# Analog_Buck.net
KiCad netlist of a schematic drawn in EasyEDA Pro
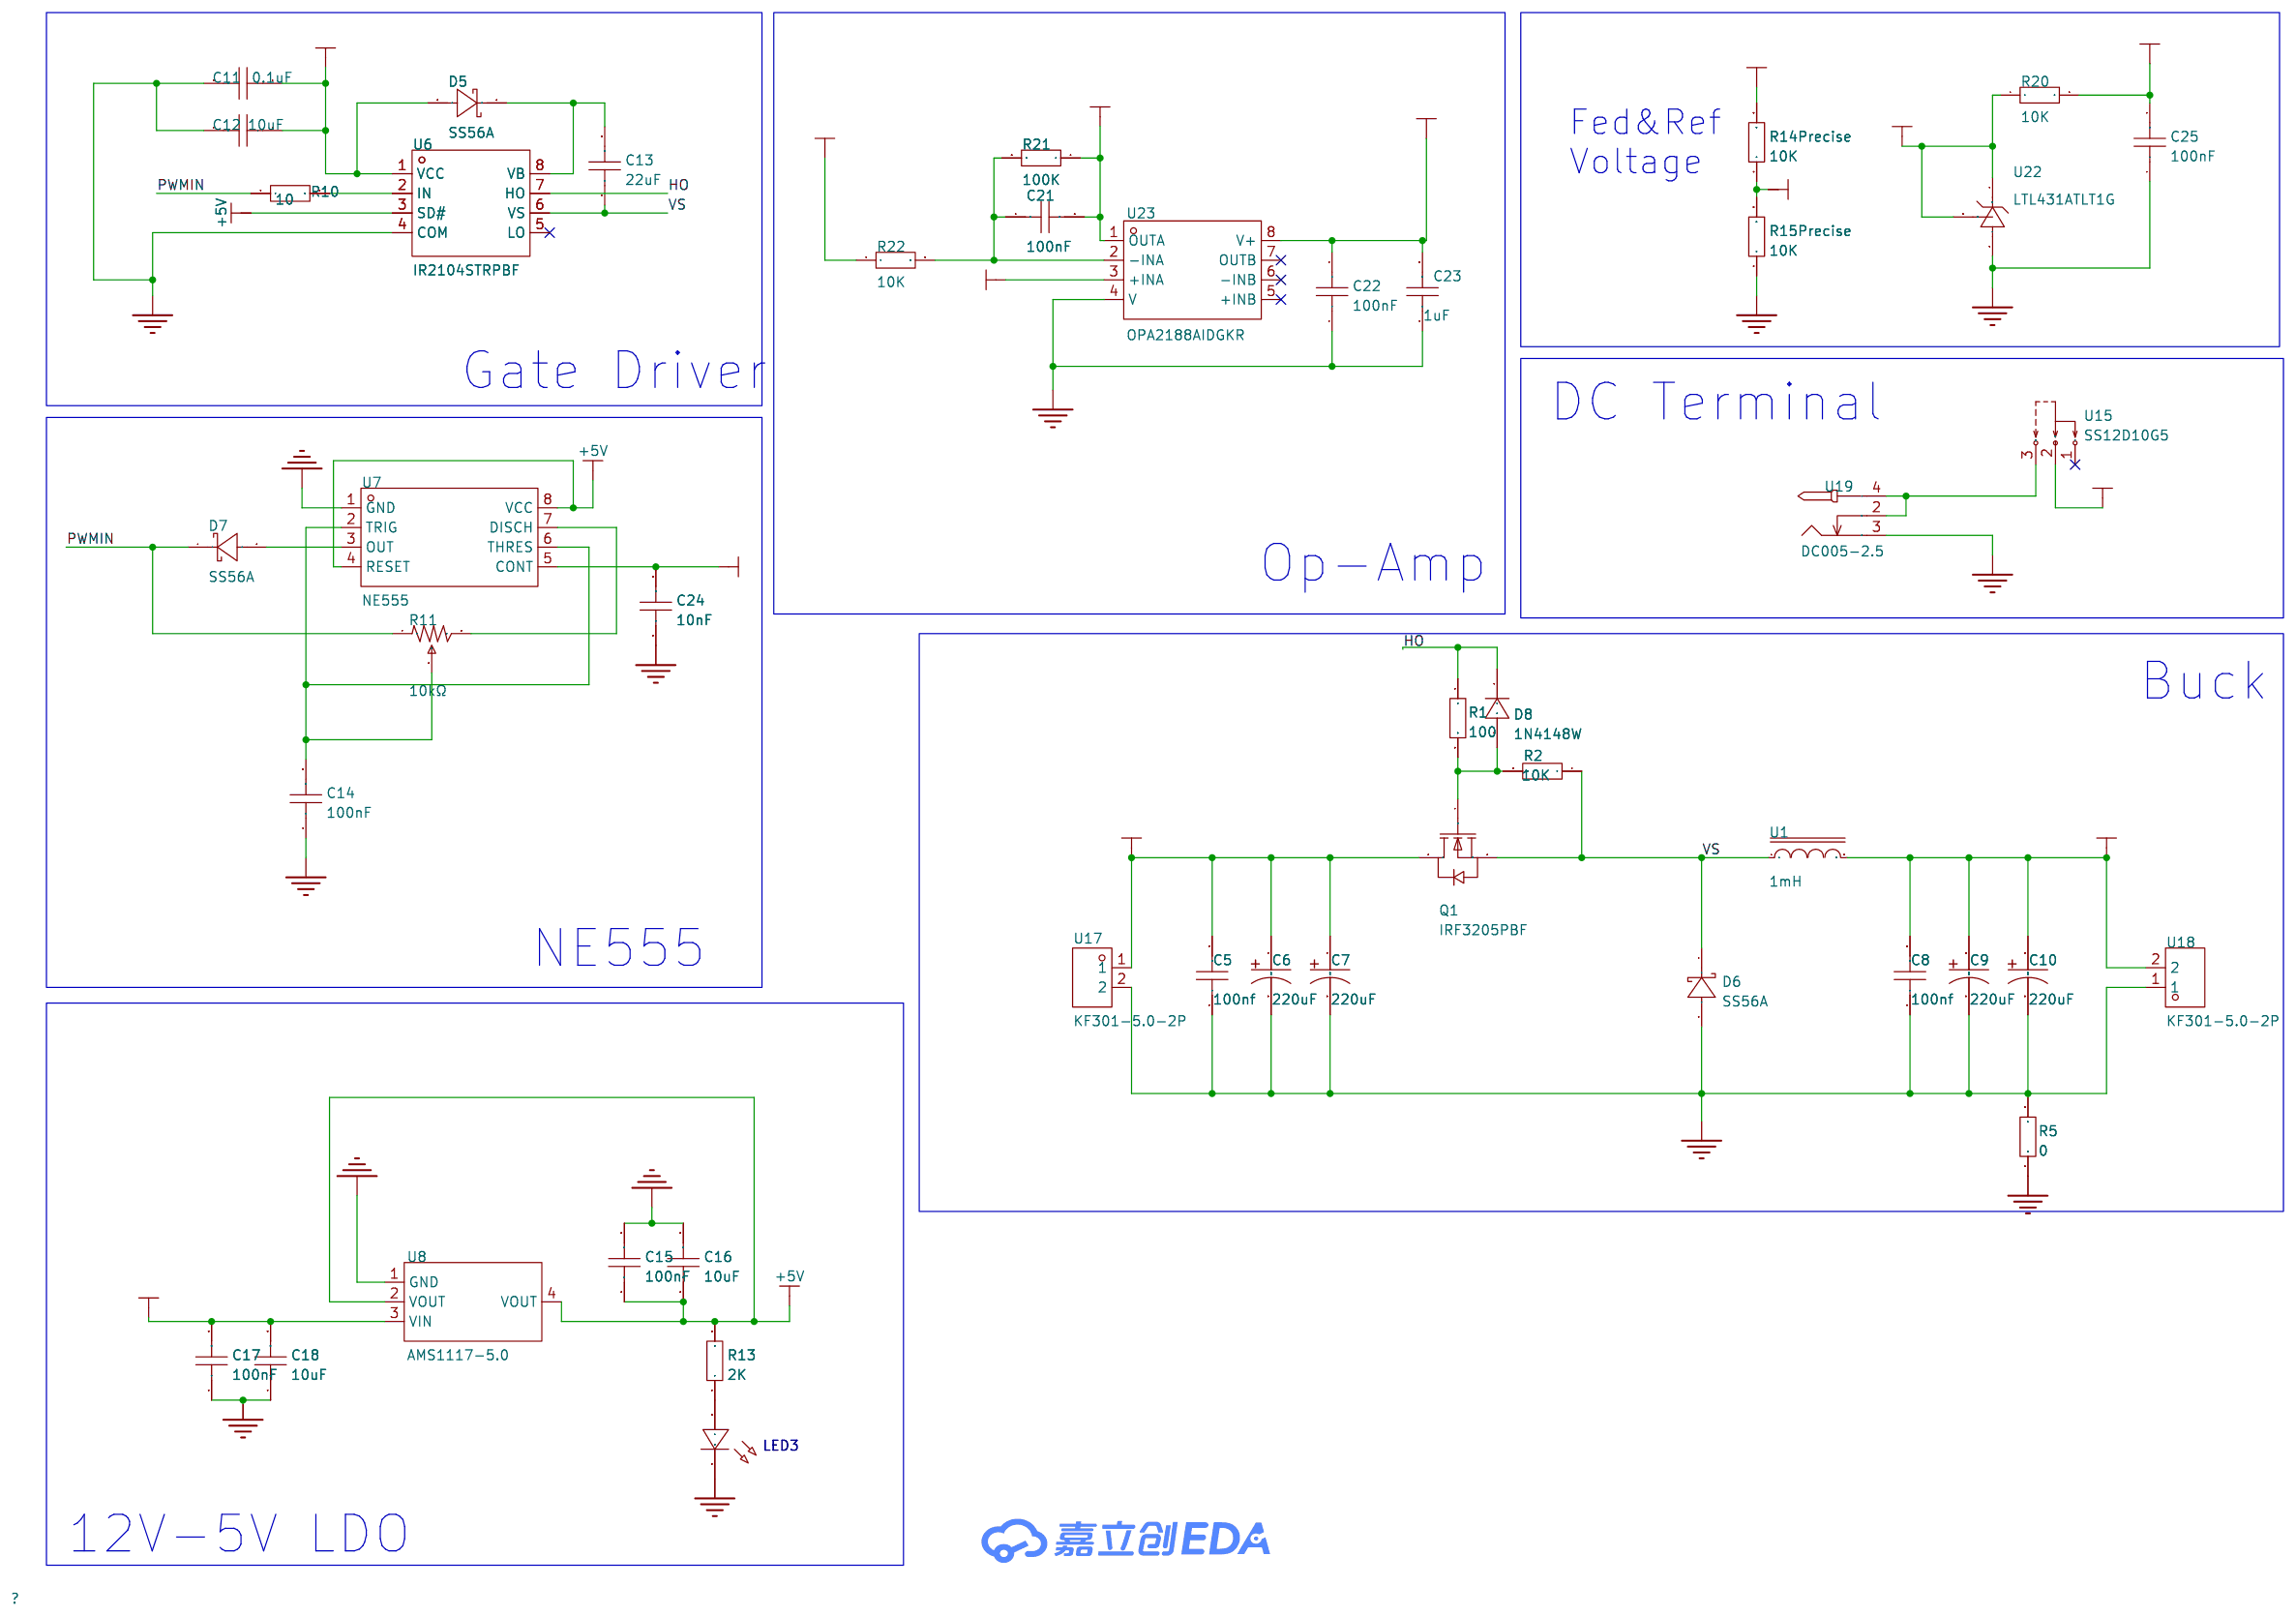
[diagram p0: schematic sheet]

(export (version "E")
  (design (tool "Eeschema 10.0.6"))
  (components
    (comp (ref "C5")
      (value "100nf")
      (footprint "easyedapro:CAP-TH_L8.5-W5.0-P5.00-D1.2")
      (description "容值:100nF;精度:±10%;额定电压:50V;温度系数:X7R;")
      (fields (field (name "Manufacturer Part") "CT4-0805B104K500F3") (field (name "Manufacturer") "FH(风华)"))
      (libsource (lib "easyedapro") (part "CT4-0805B104K500F3"))
    )
    (comp (ref "C6")
      (value "220uF")
      (footprint "easyedapro:CAP-TH_BD10.0-P5.00-D1.0-FD")
      (description "容值:220uF;精度:±20%;额定电压:100V;纹波电流:-;等效串联电阻:-;")
      (fields
        (field (name "Manufacturer Part") "ECF1JM221G17OTPO")
        (field (name "Manufacturer") "Yunxing(云星)")
      )
      (libsource (lib "easyedapro") (part "LKME2502A221MF"))
    )
    (comp (ref "C7")
      (value "220uF")
      (footprint "easyedapro:CAP-TH_BD10.0-P5.00-D1.0-FD")
      (description "容值:220uF;精度:±20%;额定电压:100V;纹波电流:-;等效串联电阻:-;")
      (fields
        (field (name "Manufacturer Part") "ECF1JM221G17OTPO")
        (field (name "Manufacturer") "Yunxing(云星)")
      )
      (libsource (lib "easyedapro") (part "LKME2502A221MF"))
    )
    (comp (ref "C8")
      (value "100nf")
      (footprint "easyedapro:CAP-TH_L8.5-W5.0-P5.00-D1.2")
      (description "容值:100nF;精度:±10%;额定电压:50V;温度系数:X7R;")
      (fields (field (name "Manufacturer Part") "CT4-0805B104K500F3") (field (name "Manufacturer") "FH(风华)"))
      (libsource (lib "easyedapro") (part "CT4-0805B104K500F3"))
    )
    (comp (ref "C9")
      (value "220uF")
      (footprint "easyedapro:CAP-TH_BD10.0-P5.00-D1.0-FD")
      (description "容值:220uF;精度:±20%;额定电压:100V;纹波电流:-;等效串联电阻:-;")
      (fields
        (field (name "Manufacturer Part") "ECF1JM221G17OTPO")
        (field (name "Manufacturer") "Yunxing(云星)")
      )
      (libsource (lib "easyedapro") (part "LKME2502A221MF"))
    )
    (comp (ref "C10")
      (value "220uF")
      (footprint "easyedapro:CAP-TH_BD10.0-P5.00-D1.0-FD")
      (description "容值:220uF;精度:±20%;额定电压:100V;纹波电流:-;等效串联电阻:-;")
      (fields
        (field (name "Manufacturer Part") "ECF1JM221G17OTPO")
        (field (name "Manufacturer") "Yunxing(云星)")
      )
      (libsource (lib "easyedapro") (part "LKME2502A221MF"))
    )
    (comp (ref "C11")
      (value "0.1uF")
      (footprint "easyedapro:C0603")
      (libsource (lib "easyedapro") (part "Capacitance"))
    )
    (comp (ref "C12")
      (value "10uF")
      (footprint "easyedapro:C0603")
      (libsource (lib "easyedapro") (part "Capacitance"))
    )
    (comp (ref "C13")
      (value "22uF")
      (fields
        (field (name "Manufacturer Part") "CD1H225KC9BER1F100")
        (field (name "Manufacturer") "Dersonic(德尔创)")
      )
      (libsource (lib "easyedapro") (part "CT40805B104K500F3"))
    )
    (comp (ref "C14")
      (value "100nF")
      (footprint "easyedapro:C0603")
      (libsource (lib "easyedapro") (part "Capacitance"))
    )
    (comp (ref "C15")
      (value "100nF")
      (footprint "easyedapro:C0603")
      (libsource (lib "easyedapro") (part "Capacitance"))
    )
    (comp (ref "C16")
      (value "10uF")
      (footprint "easyedapro:C0603")
      (libsource (lib "easyedapro") (part "Capacitance"))
    )
    (comp (ref "C17")
      (value "100nF")
      (footprint "easyedapro:C0603")
      (libsource (lib "easyedapro") (part "Capacitance"))
    )
    (comp (ref "C18")
      (value "10uF")
      (footprint "easyedapro:C0603")
      (libsource (lib "easyedapro") (part "Capacitance"))
    )
    (comp (ref "C21")
      (value "100nF")
      (footprint "easyedapro:C0603")
      (libsource (lib "easyedapro") (part "Capacitance"))
    )
    (comp (ref "C22") (value "100nF") (libsource (lib "easyedapro") (part "CapAcitance")))
    (comp (ref "C23") (value "1uF") (libsource (lib "easyedapro") (part "CapAcitance")))
    (comp (ref "C24")
      (value "10nF")
      (footprint "easyedapro:C0603")
      (libsource (lib "easyedapro") (part "Capacitance"))
    )
    (comp (ref "C25") (value "100nF") (libsource (lib "easyedapro") (part "CapAcitance")))
    (comp (ref "D5")
      (value "SS56A")
      (footprint "easyedapro:SMA_L4.2-W2.6-LS5.0-RD")
      (description "二极管配置:独立式;正向压降(Vf):700mV@5A;直流反向耐压(Vr):60V;整流电流:5A;")
      (fields (field (name "Manufacturer") "FUXINSEMI(富芯森美)"))
      (libsource (lib "easyedapro") (part "SS56A"))
    )
    (comp (ref "D6")
      (value "SS56A")
      (footprint "easyedapro:SMA_L4.2-W2.6-LS5.0-RD")
      (description "二极管配置:独立式;正向压降(Vf):700mV@5A;直流反向耐压(Vr):60V;整流电流:5A;")
      (fields (field (name "Manufacturer") "FUXINSEMI(富芯森美)"))
      (libsource (lib "easyedapro") (part "SS56A"))
    )
    (comp (ref "D7")
      (value "SS56A")
      (footprint "easyedapro:SMA_L4.2-W2.6-LS5.0-RD")
      (description "二极管配置:独立式;正向压降(Vf):700mV@5A;直流反向耐压(Vr):60V;整流电流:5A;")
      (fields (field (name "Manufacturer") "FUXINSEMI(富芯森美)"))
      (libsource (lib "easyedapro") (part "SS56A"))
    )
    (comp (ref "D8")
      (value "1N4148W")
      (footprint "easyedapro:SOD-123F_L2.7-W1.6-LS3.8-RD")
      (description "二极管配置:独立式;正向压降(Vf):1V@50mA;直流反向耐压(Vr):75V;整流电流:150mA;反向恢复时间(Trr):4ns;")
      (fields (field (name "Manufacturer") "ST(先科)"))
      (libsource (lib "easyedapro") (part "1N4148W_C81598"))
    )
    (comp (ref "LED3")
      (value "~")
      (footprint "easyedapro:LED_0805")
      (libsource (lib "easyedapro") (part "LED_G"))
    )
    (comp (ref "Q1")
      (value "IRF3205PBF")
      (footprint "easyedapro:TO-220-3_L10.0-W4.5-P2.54-L")
      (fields (field (name "Manufacturer") "Infineon(英飞凌)"))
      (libsource (lib "easyedapro") (part "IRF3205PBF"))
    )
    (comp (ref "R1") (value "100") (footprint "easyedapro:R0603") (libsource (lib "easyedapro") (part "电阻")))
    (comp (ref "R2") (value "10K") (footprint "easyedapro:R0603") (libsource (lib "easyedapro") (part "电阻")))
    (comp (ref "R5") (value "0") (footprint "easyedapro:R0603") (libsource (lib "easyedapro") (part "电阻")))
    (comp (ref "R10") (value "10") (footprint "easyedapro:R0603") (libsource (lib "easyedapro") (part "电阻")))
    (comp (ref "R11")
      (value "10kΩ")
      (footprint "easyedapro:RES-ADJ-TH_3P-L9.5-W4.9-P2.50-L_3296W")
      (description "阻值:10kΩ;精度:±10%;功率:500mW;温度系数:±250ppm/°C;")
      (fields (field (name "Manufacturer Part") "3296W-1-103LF") (field (name "Manufacturer") "JIERR(捷而瑞)"))
      (libsource (lib "easyedapro") (part "3296W-1-103LF_C49190453"))
    )
    (comp (ref "R13") (value "2K") (footprint "easyedapro:R0603") (libsource (lib "easyedapro") (part "电阻")))
    (comp (ref "R14Precise")
      (value "10K")
      (footprint "easyedapro:R0603")
      (libsource (lib "easyedapro") (part "电阻"))
    )
    (comp (ref "R15Precise")
      (value "10K")
      (footprint "easyedapro:R0603")
      (libsource (lib "easyedapro") (part "电阻"))
    )
    (comp (ref "R20") (value "10K") (footprint "easyedapro:R0603") (libsource (lib "easyedapro") (part "电阻")))
    (comp (ref "R21")
      (value "100K")
      (footprint "easyedapro:R0603")
      (libsource (lib "easyedapro") (part "电阻"))
    )
    (comp (ref "R22") (value "10K") (footprint "easyedapro:R0603") (libsource (lib "easyedapro") (part "电阻")))
    (comp (ref "U1")
      (value "1mH")
      (footprint "easyedapro:IND-TH_L33.0-W15.6-P15.00-D1.5")
      (description "电感值:47uH;精度:±10%;额定电流:12A;类型:磁环电感;")
      (fields (field (name "Manufacturer Part") "XR106125TS470MV1L5") (field (name "Manufacturer") "XR(祥如)"))
      (libsource (lib "easyedapro") (part "XR106125TS470MV1L5"))
    )
    (comp (ref "U6")
      (value "IR2104STRPBF")
      (footprint "easyedapro:SOIC-8_L4.9-W3.9-P1.27-LS6.0-BL")
      (fields (field (name "Manufacturer") "Infineon(英飞凌)"))
      (libsource (lib "easyedapro") (part "IR2104STRPBF"))
    )
    (comp (ref "U7")
      (value "NE555")
      (footprint "easyedapro:SOP-8_L5.0-W4.0-P1.27-LS6.0-BL")
      (libsource (lib "easyedapro") (part "NE555"))
    )
    (comp (ref "U8")
      (value "AMS1117-5.0")
      (footprint "easyedapro:SOT-223_L6.5-W3.5-P2.30-LS7.0-BR")
      (description "输出类型:固定;工作电压:15V;输出电压:5V;输出电流:1A;电源纹波抑制比(PSRR):60dB;输出极性:正极;")
      (fields (field (name "Manufacturer") "AMS"))
      (libsource (lib "easyedapro") (part "AMS1117-5.0"))
    )
    (comp (ref "U15")
      (value "SS12D10G5")
      (footprint "easyedapro:SW-TH_SHOU-HAN_SS12D10G4")
      (description "电路结构:单刀双掷;安装方式:直插;额定电流:2A;额定电压:125V;工作寿命:3千次;")
      (fields (field (name "Manufacturer") "SHOU HAN(首韩)"))
      (libsource (lib "easyedapro") (part "SS12D10G5"))
    )
    (comp (ref "U17")
      (value "KF301-5.0-2P")
      (footprint "easyedapro:CONN-TH_P5.00_KF301-5.0-2P")
      (fields (field (name "Manufacturer") "KEFA(科发)"))
      (libsource (lib "easyedapro") (part "KF301-5.0-2P"))
    )
    (comp (ref "U18")
      (value "KF301-5.0-2P")
      (footprint "easyedapro:CONN-TH_P5.00_KF301-5.0-2P")
      (fields (field (name "Manufacturer") "KEFA(科发)"))
      (libsource (lib "easyedapro") (part "KF301-5.0-2P"))
    )
    (comp (ref "U19")
      (value "DC005-2.5")
      (footprint "easyedapro:DC-IN-TH_DC005-2.5MM")
      (description "连接器类型:DC电源插座;安装方式:弯插;触点内径:2.5mm;触点外径:6.3mm;额定电流:500mA;额定电压:30V;工作温度:-25°C~+70°C;")
      (fields (field (name "Manufacturer") "SHOU HAN(首韩)"))
      (libsource (lib "easyedapro") (part "DC005-2.5"))
    )
    (comp (ref "U22")
      (value "LTL431ATLT1G")
      (footprint "easyedapro:SOT-23-3_L2.9-W1.3-P1.90-LS2.4-BR")
      (description "输出类型:可编程;输出电压:2.5V~36V;输出电流:100mA;最小阴极电流调节:1mA;工作温度:-40°C~+125°C@(TA);")
      (fields (field (name "Manufacturer") "LRC(乐山无线电)"))
      (libsource (lib "easyedapro") (part "LTL431ATLT1G"))
    )
    (comp (ref "U23")
      (value "OPA2188AIDGKR")
      (footprint "easyedapro:VSSOP-8_L3.0-W3.0-P0.65-LS4.9-BL")
      (description "放大器数:双路;增益带宽积(GBP):2MHz;输入偏置电流(Ib):160pA;输入失调电压(Vos):6uV;压摆率(SR):0.8V/us;轨到轨:-;")
      (fields (field (name "Manufacturer") "TI(德州仪器)"))
      (libsource (lib "easyedapro") (part "OPA2188AIDGKR"))
    )
  )
  (nets
    (net (code "1") (name "+5V") (class "Default")
      (node (ref "C15") (pin "1") (pinfunction "1_1") (pintype "input"))
      (node (ref "C16") (pin "1") (pinfunction "1_1") (pintype "input"))
      (node (ref "R13") (pin "2") (pinfunction "2_2") (pintype "input"))
      (node (ref "U6") (pin "3") (pinfunction "SD#_3") (pintype "unspecified"))
      (node (ref "U7") (pin "4") (pinfunction "RESET_4") (pintype "unspecified"))
      (node (ref "U7") (pin "8") (pinfunction "VCC_8") (pintype "unspecified"))
      (node (ref "U8") (pin "2") (pinfunction "VOUT_2") (pintype "unspecified"))
      (node (ref "U8") (pin "4") (pinfunction "VOUT_4") (pintype "unspecified"))
    )
    (net (code "2") (name "+12V") (class "Default")
      (node (ref "C11") (pin "1") (pinfunction "1_1") (pintype "input"))
      (node (ref "C12") (pin "1") (pinfunction "1_1") (pintype "input"))
      (node (ref "C17") (pin "2") (pinfunction "2_2") (pintype "input"))
      (node (ref "C18") (pin "2") (pinfunction "2_2") (pintype "input"))
      (node (ref "C22") (pin "2") (pinfunction "2_2") (pintype "input"))
      (node (ref "C23") (pin "2") (pinfunction "2_2") (pintype "input"))
      (node (ref "C25") (pin "2") (pinfunction "2_2") (pintype "input"))
      (node (ref "D5") (pin "2") (pinfunction "A_2") (pintype "unspecified"))
      (node (ref "R20") (pin "2") (pinfunction "2_2") (pintype "input"))
      (node (ref "U15") (pin "2") (pinfunction "2_2") (pintype "unspecified"))
      (node (ref "U23") (pin "8") (pinfunction "V+_8") (pintype "unspecified"))
      (node (ref "U6") (pin "1") (pinfunction "VCC_1") (pintype "unspecified"))
      (node (ref "U8") (pin "3") (pinfunction "VIN_3") (pintype "unspecified"))
    )
    (net (code "3") (name "/HO") (class "Default")
      (node (ref "D8") (pin "1") (pinfunction "K_1") (pintype "unspecified"))
      (node (ref "R1") (pin "1") (pinfunction "1_1") (pintype "input"))
      (node (ref "U6") (pin "7") (pinfunction "HO_7") (pintype "unspecified"))
    )
    (net (code "4") (name "/PWMIN") (class "Default")
      (node (ref "D7") (pin "1") (pinfunction "K_1") (pintype "unspecified"))
      (node (ref "R10") (pin "1") (pinfunction "1_1") (pintype "input"))
      (node (ref "R11") (pin "1") (pinfunction "1_1") (pintype "unspecified"))
    )
    (net (code "5") (name "/VS") (class "Default")
      (node (ref "C13") (pin "1") (pinfunction "1_1") (pintype "unspecified"))
      (node (ref "D6") (pin "1") (pinfunction "K_1") (pintype "unspecified"))
      (node (ref "Q1") (pin "3") (pinfunction "S_3") (pintype "unspecified"))
      (node (ref "R2") (pin "1") (pinfunction "1_1") (pintype "input"))
      (node (ref "U1") (pin "1") (pinfunction "1_1") (pintype "unspecified"))
      (node (ref "U6") (pin "6") (pinfunction "VS_6") (pintype "unspecified"))
    )
    (net (code "6") (name "DGND") (class "Default")
      (node (ref "C11") (pin "2") (pinfunction "2_2") (pintype "input"))
      (node (ref "C12") (pin "2") (pinfunction "2_2") (pintype "input"))
      (node (ref "C14") (pin "1") (pinfunction "1_1") (pintype "input"))
      (node (ref "C15") (pin "2") (pinfunction "2_2") (pintype "input"))
      (node (ref "C16") (pin "2") (pinfunction "2_2") (pintype "input"))
      (node (ref "C17") (pin "1") (pinfunction "1_1") (pintype "input"))
      (node (ref "C18") (pin "1") (pinfunction "1_1") (pintype "input"))
      (node (ref "C22") (pin "1") (pinfunction "1_1") (pintype "input"))
      (node (ref "C23") (pin "1") (pinfunction "1_1") (pintype "input"))
      (node (ref "C24") (pin "1") (pinfunction "1_1") (pintype "input"))
      (node (ref "C25") (pin "1") (pinfunction "1_1") (pintype "input"))
      (node (ref "LED3") (pin "1") (pinfunction "C_1") (pintype "input"))
      (node (ref "R5") (pin "1") (pinfunction "1_1") (pintype "input"))
      (node (ref "U19") (pin "3") (pinfunction "3_3") (pintype "unspecified"))
      (node (ref "U22") (pin "3") (pinfunction "A_3") (pintype "input"))
      (node (ref "U23") (pin "4") (pinfunction "V_4") (pintype "unspecified"))
      (node (ref "U6") (pin "4") (pinfunction "COM_4") (pintype "unspecified"))
      (node (ref "U7") (pin "1") (pinfunction "GND_1") (pintype "unspecified"))
      (node (ref "U8") (pin "1") (pinfunction "GND_1") (pintype "unspecified"))
    )
    (net (code "7") (name "GND") (class "Default")
      (node (ref "C10") (pin "2") (pinfunction "2_2") (pintype "unspecified"))
      (node (ref "C5") (pin "1") (pinfunction "1_1") (pintype "unspecified"))
      (node (ref "C6") (pin "2") (pinfunction "2_2") (pintype "unspecified"))
      (node (ref "C7") (pin "2") (pinfunction "2_2") (pintype "unspecified"))
      (node (ref "C8") (pin "1") (pinfunction "1_1") (pintype "unspecified"))
      (node (ref "C9") (pin "2") (pinfunction "2_2") (pintype "unspecified"))
      (node (ref "D6") (pin "2") (pinfunction "A_2") (pintype "unspecified"))
      (node (ref "R15Precise") (pin "1") (pinfunction "1_1") (pintype "input"))
      (node (ref "R5") (pin "2") (pinfunction "2_2") (pintype "input"))
      (node (ref "U17") (pin "2") (pinfunction "2_2") (pintype "unspecified"))
      (node (ref "U18") (pin "1") (pinfunction "1_1") (pintype "unspecified"))
    )
    (net (code "8") (name "Net-(D5-K)") (class "Default")
      (node (ref "C13") (pin "2") (pinfunction "2_2") (pintype "unspecified"))
      (node (ref "D5") (pin "1") (pinfunction "K_1") (pintype "unspecified"))
      (node (ref "U6") (pin "8") (pinfunction "VB_8") (pintype "unspecified"))
    )
    (net (code "9") (name "Net-(D7-A)") (class "Default")
      (node (ref "D7") (pin "2") (pinfunction "A_2") (pintype "unspecified"))
      (node (ref "U7") (pin "3") (pinfunction "OUT_3") (pintype "unspecified"))
    )
    (net (code "10") (name "Net-(D8-A)") (class "Default")
      (node (ref "D8") (pin "2") (pinfunction "A_2") (pintype "unspecified"))
      (node (ref "Q1") (pin "1") (pinfunction "G_1") (pintype "unspecified"))
      (node (ref "R1") (pin "2") (pinfunction "2_2") (pintype "input"))
      (node (ref "R2") (pin "2") (pinfunction "2_2") (pintype "input"))
    )
    (net (code "11") (name "Net-(LED3-A)") (class "Default")
      (node (ref "LED3") (pin "2") (pinfunction "A_2") (pintype "input"))
      (node (ref "R13") (pin "1") (pinfunction "1_1") (pintype "input"))
    )
    (net (code "12") (name "Net-(U6-IN)") (class "Default")
      (node (ref "R10") (pin "2") (pinfunction "2_2") (pintype "input"))
      (node (ref "U6") (pin "2") (pinfunction "IN_2") (pintype "unspecified"))
    )
    (net (code "13") (name "Net-(U7-DISCH)") (class "Default")
      (node (ref "R11") (pin "3") (pinfunction "3_3") (pintype "unspecified"))
      (node (ref "U7") (pin "7") (pinfunction "DISCH_7") (pintype "unspecified"))
    )
    (net (code "14") (name "Net-(U7-THRES)") (class "Default")
      (node (ref "C14") (pin "2") (pinfunction "2_2") (pintype "input"))
      (node (ref "R11") (pin "2") (pinfunction "2_2") (pintype "unspecified"))
      (node (ref "U7") (pin "2") (pinfunction "TRIG_2") (pintype "unspecified"))
      (node (ref "U7") (pin "6") (pinfunction "THRES_6") (pintype "unspecified"))
    )
    (net (code "15") (name "Net-(U15-Pad3)") (class "Default")
      (node (ref "U15") (pin "3") (pinfunction "3_3") (pintype "unspecified"))
      (node (ref "U19") (pin "2") (pinfunction "2_2") (pintype "unspecified"))
      (node (ref "U19") (pin "4") (pinfunction "4_4") (pintype "unspecified"))
    )
    (net (code "16") (name "Net-(U23--INA)") (class "Default")
      (node (ref "C21") (pin "1") (pinfunction "1_1") (pintype "input"))
      (node (ref "R21") (pin "2") (pinfunction "2_2") (pintype "input"))
      (node (ref "R22") (pin "2") (pinfunction "2_2") (pintype "input"))
      (node (ref "U23") (pin "2") (pinfunction "-INA_2") (pintype "unspecified"))
    )
    (net (code "17") (name "VCON") (class "Default")
      (node (ref "C21") (pin "2") (pinfunction "2_2") (pintype "input"))
      (node (ref "C24") (pin "2") (pinfunction "2_2") (pintype "input"))
      (node (ref "R21") (pin "1") (pinfunction "1_1") (pintype "input"))
      (node (ref "U23") (pin "1") (pinfunction "OUTA_1") (pintype "unspecified"))
      (node (ref "U7") (pin "5") (pinfunction "CONT_5") (pintype "unspecified"))
    )
    (net (code "18") (name "VFB") (class "Default")
      (node (ref "R14Precise") (pin "1") (pinfunction "1_1") (pintype "input"))
      (node (ref "R15Precise") (pin "2") (pinfunction "2_2") (pintype "input"))
      (node (ref "R22") (pin "1") (pinfunction "1_1") (pintype "input"))
    )
    (net (code "19") (name "VIN") (class "Default")
      (node (ref "C5") (pin "2") (pinfunction "2_2") (pintype "unspecified"))
      (node (ref "C6") (pin "1") (pinfunction "1_1") (pintype "unspecified"))
      (node (ref "C7") (pin "1") (pinfunction "1_1") (pintype "unspecified"))
      (node (ref "Q1") (pin "2") (pinfunction "D_2") (pintype "unspecified"))
      (node (ref "U17") (pin "1") (pinfunction "1_1") (pintype "unspecified"))
    )
    (net (code "20") (name "VOUT") (class "Default")
      (node (ref "C10") (pin "1") (pinfunction "1_1") (pintype "unspecified"))
      (node (ref "C8") (pin "2") (pinfunction "2_2") (pintype "unspecified"))
      (node (ref "C9") (pin "1") (pinfunction "1_1") (pintype "unspecified"))
      (node (ref "R14Precise") (pin "2") (pinfunction "2_2") (pintype "input"))
      (node (ref "U1") (pin "2") (pinfunction "2_2") (pintype "unspecified"))
      (node (ref "U18") (pin "2") (pinfunction "2_2") (pintype "unspecified"))
    )
    (net (code "21") (name "VREF") (class "Default")
      (node (ref "R20") (pin "1") (pinfunction "1_1") (pintype "input"))
      (node (ref "U22") (pin "1") (pinfunction "C_1") (pintype "input"))
      (node (ref "U22") (pin "2") (pinfunction "REF_2") (pintype "input"))
      (node (ref "U23") (pin "3") (pinfunction "+INA_3") (pintype "unspecified"))
    )
    (net (code "22") (name "unconnected-(U6-LO-Pad5)") (class "Default")
      (node (ref "U6") (pin "5") (pinfunction "LO_5") (pintype "unspecified+no_connect"))
    )
    (net (code "23") (name "unconnected-(U15-Pad1)") (class "Default")
      (node (ref "U15") (pin "1") (pinfunction "1_1") (pintype "unspecified+no_connect"))
    )
    (net (code "24") (name "unconnected-(U23-+INB-Pad5)") (class "Default")
      (node (ref "U23") (pin "5") (pinfunction "+INB_5") (pintype "unspecified+no_connect"))
    )
    (net (code "25") (name "unconnected-(U23--INB-Pad6)") (class "Default")
      (node (ref "U23") (pin "6") (pinfunction "-INB_6") (pintype "unspecified+no_connect"))
    )
    (net (code "26") (name "unconnected-(U23-OUTB-Pad7)") (class "Default")
      (node (ref "U23") (pin "7") (pinfunction "OUTB_7") (pintype "unspecified+no_connect"))
    )
  )
)
